# HeartBeat.net
KiCad netlist of a schematic drawn in Altium Designer
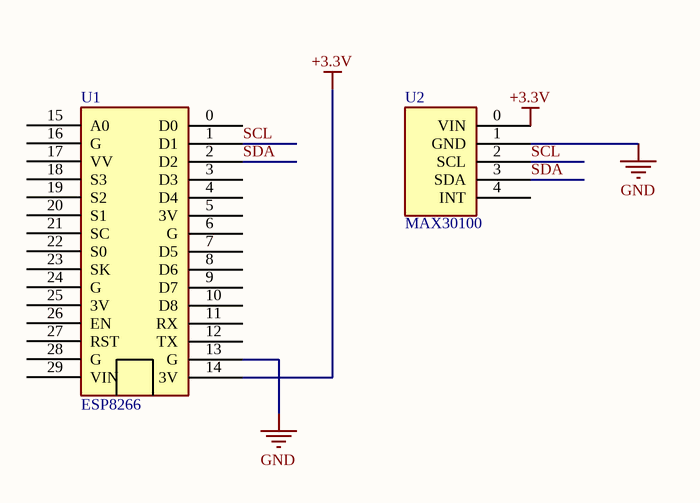
[diagram p0: HeartBeat.SchDoc]

(export (version "E")
  (design (tool "Eeschema 10.0.6"))
  (components
    (comp (ref "U1")
      (value "ESP8266")
      (footprint "ESP8266")
      (description "ESP8266-12E")
      (libsource (lib "Integrated_Library1") (part "ESP8266"))
    )
    (comp (ref "U2")
      (value "MAX30100")
      (footprint "MAX30100")
      (description "MAX30100-GY")
      (libsource (lib "Integrated_Library1") (part "MAX30100"))
    )
  )
  (nets
    (net (code "1") (name "+3.3V") (class "Default")
      (node (ref "U1") (pin "14") (pinfunction "3V_14") (pintype "passive"))
      (node (ref "U2") (pin "0") (pinfunction "VIN_0") (pintype "passive"))
    )
    (net (code "2") (name "/SCL") (class "Default")
      (node (ref "U1") (pin "1") (pinfunction "D1_1") (pintype "passive"))
      (node (ref "U2") (pin "2") (pinfunction "SCL_2") (pintype "passive"))
    )
    (net (code "3") (name "/SDA") (class "Default")
      (node (ref "U1") (pin "2") (pinfunction "D2_2") (pintype "passive"))
      (node (ref "U2") (pin "3") (pinfunction "SDA_3") (pintype "passive"))
    )
    (net (code "4") (name "GND") (class "Default")
      (node (ref "U1") (pin "13") (pinfunction "G_13") (pintype "passive"))
      (node (ref "U2") (pin "1") (pinfunction "GND_1") (pintype "passive"))
    )
    (net (code "5") (name "unconnected-(U1-3V-Pad5)") (class "Default")
      (node (ref "U1") (pin "5") (pinfunction "3V_5") (pintype "passive"))
    )
    (net (code "6") (name "unconnected-(U1-3V-Pad25)") (class "Default")
      (node (ref "U1") (pin "25") (pinfunction "3V_25") (pintype "passive"))
    )
    (net (code "7") (name "unconnected-(U1-A0-Pad15)") (class "Default")
      (node (ref "U1") (pin "15") (pinfunction "A0_15") (pintype "passive"))
    )
    (net (code "8") (name "unconnected-(U1-D0-Pad0)") (class "Default")
      (node (ref "U1") (pin "0") (pinfunction "D0_0") (pintype "passive"))
    )
    (net (code "9") (name "unconnected-(U1-D3-Pad3)") (class "Default")
      (node (ref "U1") (pin "3") (pinfunction "D3_3") (pintype "passive"))
    )
    (net (code "10") (name "unconnected-(U1-D4-Pad4)") (class "Default")
      (node (ref "U1") (pin "4") (pinfunction "D4_4") (pintype "passive"))
    )
    (net (code "11") (name "unconnected-(U1-D5-Pad7)") (class "Default")
      (node (ref "U1") (pin "7") (pinfunction "D5_7") (pintype "passive"))
    )
    (net (code "12") (name "unconnected-(U1-D6-Pad8)") (class "Default")
      (node (ref "U1") (pin "8") (pinfunction "D6_8") (pintype "passive"))
    )
    (net (code "13") (name "unconnected-(U1-D7-Pad9)") (class "Default")
      (node (ref "U1") (pin "9") (pinfunction "D7_9") (pintype "passive"))
    )
    (net (code "14") (name "unconnected-(U1-D8-Pad10)") (class "Default")
      (node (ref "U1") (pin "10") (pinfunction "D8_10") (pintype "passive"))
    )
    (net (code "15") (name "unconnected-(U1-EN-Pad26)") (class "Default")
      (node (ref "U1") (pin "26") (pinfunction "EN_26") (pintype "passive"))
    )
    (net (code "16") (name "unconnected-(U1-G-Pad6)") (class "Default")
      (node (ref "U1") (pin "6") (pinfunction "G_6") (pintype "passive"))
    )
    (net (code "17") (name "unconnected-(U1-G-Pad16)") (class "Default")
      (node (ref "U1") (pin "16") (pinfunction "G_16") (pintype "passive"))
    )
    (net (code "18") (name "unconnected-(U1-G-Pad24)") (class "Default")
      (node (ref "U1") (pin "24") (pinfunction "G_24") (pintype "passive"))
    )
    (net (code "19") (name "unconnected-(U1-G-Pad28)") (class "Default")
      (node (ref "U1") (pin "28") (pinfunction "G_28") (pintype "passive"))
    )
    (net (code "20") (name "unconnected-(U1-RST-Pad27)") (class "Default")
      (node (ref "U1") (pin "27") (pinfunction "RST_27") (pintype "passive"))
    )
    (net (code "21") (name "unconnected-(U1-RX-Pad11)") (class "Default")
      (node (ref "U1") (pin "11") (pinfunction "RX_11") (pintype "passive"))
    )
    (net (code "22") (name "unconnected-(U1-S0-Pad22)") (class "Default")
      (node (ref "U1") (pin "22") (pinfunction "S0_22") (pintype "passive"))
    )
    (net (code "23") (name "unconnected-(U1-S1-Pad20)") (class "Default")
      (node (ref "U1") (pin "20") (pinfunction "S1_20") (pintype "passive"))
    )
    (net (code "24") (name "unconnected-(U1-S2-Pad19)") (class "Default")
      (node (ref "U1") (pin "19") (pinfunction "S2_19") (pintype "passive"))
    )
    (net (code "25") (name "unconnected-(U1-S3-Pad18)") (class "Default")
      (node (ref "U1") (pin "18") (pinfunction "S3_18") (pintype "passive"))
    )
    (net (code "26") (name "unconnected-(U1-SC-Pad21)") (class "Default")
      (node (ref "U1") (pin "21") (pinfunction "SC_21") (pintype "passive"))
    )
    (net (code "27") (name "unconnected-(U1-SK-Pad23)") (class "Default")
      (node (ref "U1") (pin "23") (pinfunction "SK_23") (pintype "passive"))
    )
    (net (code "28") (name "unconnected-(U1-TX-Pad12)") (class "Default")
      (node (ref "U1") (pin "12") (pinfunction "TX_12") (pintype "passive"))
    )
    (net (code "29") (name "unconnected-(U1-VIN-Pad29)") (class "Default")
      (node (ref "U1") (pin "29") (pinfunction "VIN_29") (pintype "passive"))
    )
    (net (code "30") (name "unconnected-(U1-VV-Pad17)") (class "Default")
      (node (ref "U1") (pin "17") (pinfunction "VV_17") (pintype "passive"))
    )
    (net (code "31") (name "unconnected-(U2-INT-Pad4)") (class "Default")
      (node (ref "U2") (pin "4") (pinfunction "INT_4") (pintype "passive"))
    )
  )
)
